# ucus_kayit.net
KiCad netlist of a schematic drawn in Altium Designer
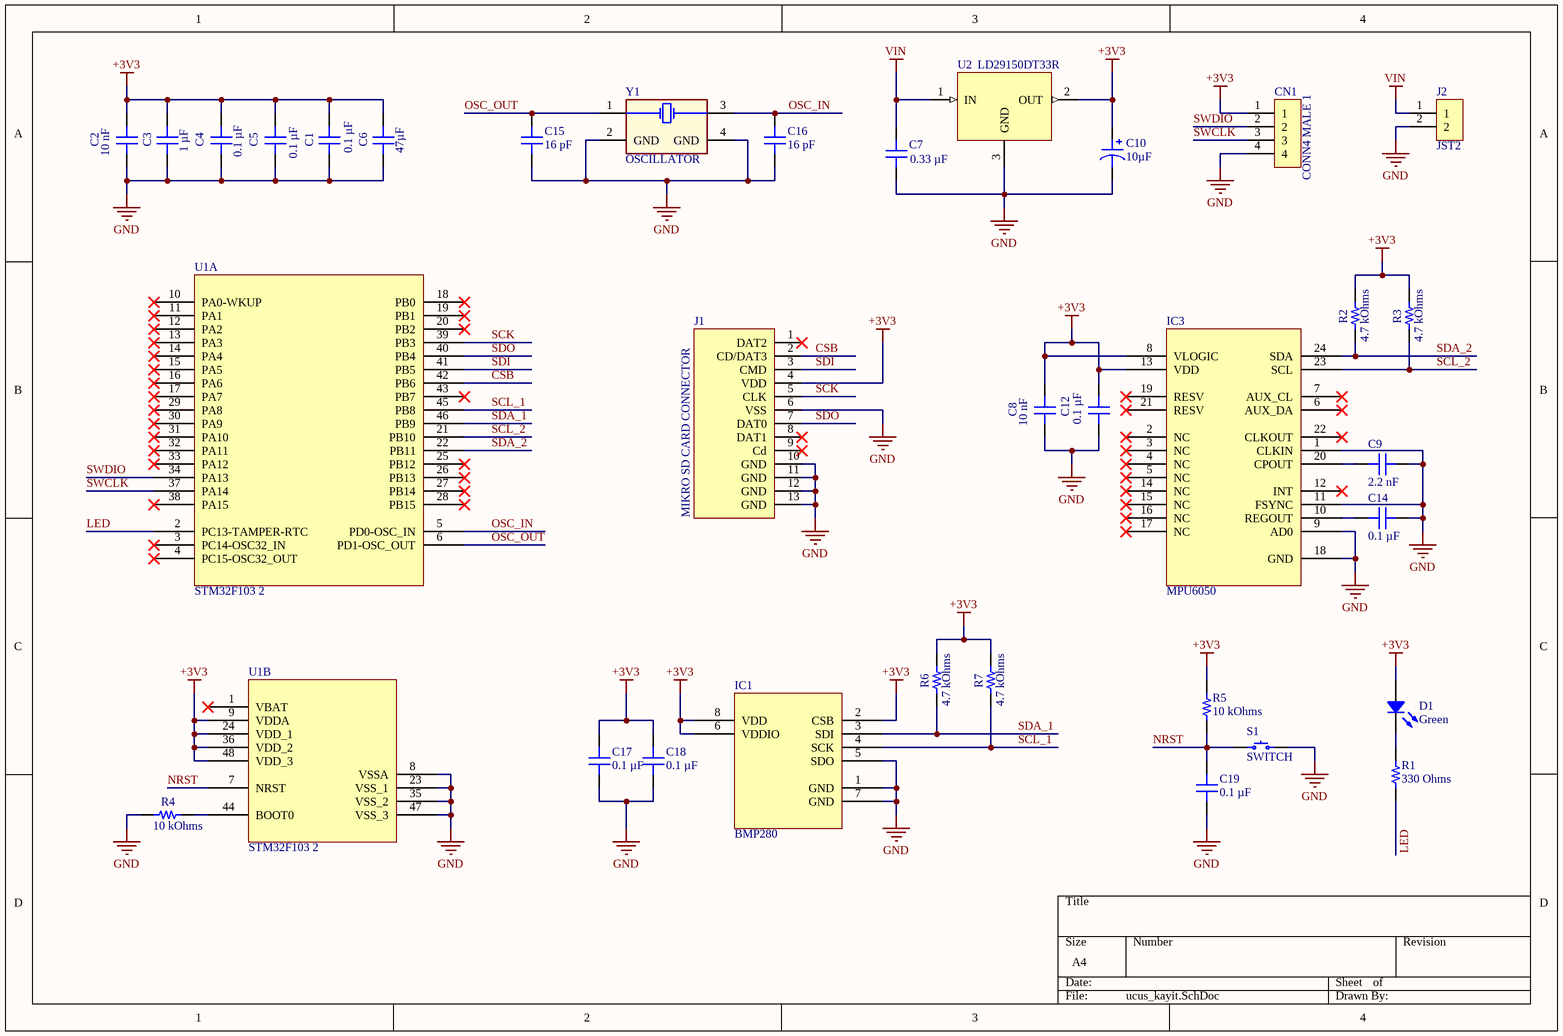
[diagram p0: ucus_kayit.SchDoc]

(export (version "E")
  (design (tool "Eeschema 10.0.6"))
  (components
    (comp (ref "C1")
      (value "0.1 µF")
      (footprint "CAP 1206_3216 - 0.8MM")
      (description "CAP CER 0.1UF 50V X7R 1206")
      (fields
        (field (name "PART NUMBER") "1206B104M500CT")
        (field (name "MANUFACTURER") "Walsin Technology Corporation")
      )
      (libsource (lib "Celestial Altium Library - altium_library") (part "Capacitor"))
    )
    (comp (ref "C2")
      (value "10 nF")
      (footprint "CAP 1206_3216 - 0.8MM")
      (description "CAP CER 1206 10NF 25V C0G 1%")
      (fields (field (name "PART NUMBER") "C1206C103F3GECAUTO") (field (name "MANUFACTURER") "KEMET"))
      (libsource (lib "Celestial Altium Library - altium_library") (part "Capacitor"))
    )
    (comp (ref "C3")
      (value "1 µF")
      (footprint "CAP 1206_3216 - 0.8MM")
      (description "CAP CER 1206 1UF 25V X7R")
      (fields (field (name "PART NUMBER") "C1206X105K3RAC3316") (field (name "MANUFACTURER") "KEMET"))
      (libsource (lib "Celestial Altium Library - altium_library") (part "Capacitor"))
    )
    (comp (ref "C4")
      (value "0.1 µF")
      (footprint "CAP 1206_3216 - 0.8MM")
      (description "CAP CER 0.1UF 50V X7R 1206")
      (fields
        (field (name "PART NUMBER") "1206B104M500CT")
        (field (name "MANUFACTURER") "Walsin Technology Corporation")
      )
      (libsource (lib "Celestial Altium Library - altium_library") (part "Capacitor"))
    )
    (comp (ref "C5")
      (value "0.1 µF")
      (footprint "CAP 1206_3216 - 0.8MM")
      (description "CAP CER 0.1UF 50V X7R 1206")
      (fields
        (field (name "PART NUMBER") "1206B104M500CT")
        (field (name "MANUFACTURER") "Walsin Technology Corporation")
      )
      (libsource (lib "Celestial Altium Library - altium_library") (part "Capacitor"))
    )
    (comp (ref "C6")
      (value "47µF")
      (footprint "CAP 1206_3216 - 1.8MM")
      (description "CAP CER 47UF 6.3V X5R 1206")
      (fields (field (name "PART NUMBER") "12066D476MAT2A") (field (name "MANUFACTURER") "AVX Corporation"))
      (libsource (lib "Celestial Altium Library - altium_library") (part "Capacitor"))
    )
    (comp (ref "C7")
      (value "0.33 µF")
      (footprint "CAP 1206_3216 - 0.8MM")
      (description "CAP CER 0.33UF 25V X7R 1206")
      (fields (field (name "PART NUMBER") "C1206X334K3RAC7800") (field (name "MANUFACTURER") "KEMET"))
      (libsource (lib "Celestial Altium Library - altium_library") (part "Capacitor"))
    )
    (comp (ref "C8")
      (value "10 nF")
      (footprint "CAP 1206_3216 - 0.8MM")
      (description "CAP CER 1206 10NF 25V C0G 1%")
      (fields (field (name "PART NUMBER") "C1206C103F3GECAUTO") (field (name "MANUFACTURER") "KEMET"))
      (libsource (lib "Celestial Altium Library - altium_library") (part "Capacitor"))
    )
    (comp (ref "C9")
      (value "2.2 nF")
      (footprint "CAP 1206_3216 - 0.8MM")
      (description "CAP CER 1206 2.2NF 50V C0G 10%")
      (fields (field (name "PART NUMBER") "C1206C222K5GEC7210") (field (name "MANUFACTURER") "KEMET"))
      (libsource (lib "Celestial Altium Library - altium_library") (part "Capacitor"))
    )
    (comp (ref "C10")
      (value "10µF")
      (footprint "CAP POL 1206_3216")
      (description "CAP TANT 10UF 20% 25V 1206")
      (fields (field (name "PART NUMBER") "F951E106MAAAQ2") (field (name "MANUFACTURER") "AVX Corporation"))
      (libsource (lib "Celestial Altium Library - altium_library") (part "Polarised Capacitor"))
    )
    (comp (ref "C12")
      (value "0.1 µF")
      (footprint "CAP 1206_3216 - 0.8MM")
      (description "CAP CER 0.1UF 50V X7R 1206")
      (fields
        (field (name "PART NUMBER") "1206B104M500CT")
        (field (name "MANUFACTURER") "Walsin Technology Corporation")
      )
      (libsource (lib "Celestial Altium Library - altium_library") (part "Capacitor"))
    )
    (comp (ref "C14")
      (value "0.1 µF")
      (footprint "CAP 1206_3216 - 0.8MM")
      (description "CAP CER 0.1UF 50V X7R 1206")
      (fields
        (field (name "PART NUMBER") "1206B104M500CT")
        (field (name "MANUFACTURER") "Walsin Technology Corporation")
      )
      (libsource (lib "Celestial Altium Library - altium_library") (part "Capacitor"))
    )
    (comp (ref "C15")
      (value "16 pF")
      (footprint "CAP 1206_3216 - 0.8MM")
      (description "CAP CER 16PF 50V NP0 1206")
      (fields (field (name "PART NUMBER") "C1206C160J5GAC7800") (field (name "MANUFACTURER") "KEMET"))
      (libsource (lib "Celestial Altium Library - altium_library") (part "Capacitor"))
    )
    (comp (ref "C16")
      (value "16 pF")
      (footprint "CAP 1206_3216 - 0.8MM")
      (description "CAP CER 16PF 50V NP0 1206")
      (fields (field (name "PART NUMBER") "C1206C160J5GAC7800") (field (name "MANUFACTURER") "KEMET"))
      (libsource (lib "Celestial Altium Library - altium_library") (part "Capacitor"))
    )
    (comp (ref "C17")
      (value "0.1 µF")
      (footprint "CAP 1206_3216 - 0.8MM")
      (description "CAP CER 0.1UF 50V X7R 1206")
      (fields
        (field (name "PART NUMBER") "1206B104M500CT")
        (field (name "MANUFACTURER") "Walsin Technology Corporation")
      )
      (libsource (lib "Celestial Altium Library - altium_library") (part "Capacitor"))
    )
    (comp (ref "C18")
      (value "0.1 µF")
      (footprint "CAP 1206_3216 - 0.8MM")
      (description "CAP CER 0.1UF 50V X7R 1206")
      (fields
        (field (name "PART NUMBER") "1206B104M500CT")
        (field (name "MANUFACTURER") "Walsin Technology Corporation")
      )
      (libsource (lib "Celestial Altium Library - altium_library") (part "Capacitor"))
    )
    (comp (ref "C19")
      (value "0.1 µF")
      (footprint "CAP 1206_3216 - 0.8MM")
      (description "CAP CER 0.1UF 50V X7R 1206")
      (fields
        (field (name "PART NUMBER") "1206B104M500CT")
        (field (name "MANUFACTURER") "Walsin Technology Corporation")
      )
      (libsource (lib "Celestial Altium Library - altium_library") (part "Capacitor"))
    )
    (comp (ref "CN1")
      (value "CONN4 MALE 1")
      (footprint "CONN4 MALE 1")
      (description "4 PIN 2.54MM")
      (libsource (lib "UcusKontrol_Library") (part "CONN4 MALE 1"))
    )
    (comp (ref "D1")
      (value "Green")
      (footprint "LED 0805_2012 GREEN")
      (description "LED GREEN 0805 SMD")
      (fields (field (name "PART NUMBER") "5975316507F") (field (name "MANUFACTURER") "Dialight"))
      (libsource (lib "Celestial Altium Library - altium_library") (part "LED"))
    )
    (comp (ref "IC1") (value "BMP280") (footprint "BMP280") (libsource (lib "ucus_kayit") (part "BMP280")))
    (comp (ref "IC3")
      (value "MPU6050")
      (footprint "QFN")
      (description "IC-6050 SENSOR MOTION QFN24")
      (libsource (lib "UcusKontrol_Library") (part "MPU6050"))
    )
    (comp (ref "J1")
      (value "MIKRO SD CARD CONNECTOR")
      (footprint "MICRO SD CARD CONNECTOR")
      (libsource (lib "UcusKontrol_Library") (part "MIKRO SD CARD CONNECTOR"))
    )
    (comp (ref "J2")
      (value "JST2")
      (footprint "JST2")
      (description "2 PIN 2.54MM")
      (libsource (lib "UcusKontrol_Library") (part "JST2"))
    )
    (comp (ref "R1")
      (value "330 Ohms")
      (footprint "RES 1206_3216")
      (description "RES 330 OHM 5% 1/4W 1206")
      (fields (field (name "PART NUMBER") "RC1206JR-07330RL") (field (name "MANUFACTURER") "Yageo"))
      (libsource (lib "Celestial Altium Library - altium_library") (part "Resistor"))
    )
    (comp (ref "R2")
      (value "4.7 kOhms")
      (footprint "RES 1206_3216")
      (description "RES 4.7K OHM 0.1% 2/5W 1206")
      (fields (field (name "PART NUMBER") "TNPW12064K70BEEA") (field (name "MANUFACTURER") "Vishay Dale"))
      (libsource (lib "Celestial Altium Library - altium_library") (part "Resistor"))
    )
    (comp (ref "R3")
      (value "4.7 kOhms")
      (footprint "RES 1206_3216")
      (description "RES 4.7K OHM 0.1% 2/5W 1206")
      (fields (field (name "PART NUMBER") "TNPW12064K70BEEA") (field (name "MANUFACTURER") "Vishay Dale"))
      (libsource (lib "Celestial Altium Library - altium_library") (part "Resistor"))
    )
    (comp (ref "R4")
      (value "10 kOhms")
      (footprint "RES 1206_3216")
      (description "RES SMD 10K OHM 1% 1/4W 1206")
      (fields (field (name "PART NUMBER") "CRCW120610K0FKTA") (field (name "MANUFACTURER") "Vishay Dale"))
      (libsource (lib "Celestial Altium Library - altium_library") (part "Resistor"))
    )
    (comp (ref "R5")
      (value "10 kOhms")
      (footprint "RES 1206_3216")
      (description "RES SMD 10K OHM 1% 1/4W 1206")
      (fields (field (name "PART NUMBER") "CRCW120610K0FKTA") (field (name "MANUFACTURER") "Vishay Dale"))
      (libsource (lib "Celestial Altium Library - altium_library") (part "Resistor"))
    )
    (comp (ref "R6")
      (value "4.7 kOhms")
      (footprint "RES 1206_3216")
      (description "RES 4.7K OHM 0.1% 2/5W 1206")
      (fields (field (name "PART NUMBER") "TNPW12064K70BEEA") (field (name "MANUFACTURER") "Vishay Dale"))
      (libsource (lib "Celestial Altium Library - altium_library") (part "Resistor"))
    )
    (comp (ref "R7")
      (value "4.7 kOhms")
      (footprint "RES 1206_3216")
      (description "RES 4.7K OHM 0.1% 2/5W 1206")
      (fields (field (name "PART NUMBER") "TNPW12064K70BEEA") (field (name "MANUFACTURER") "Vishay Dale"))
      (libsource (lib "Celestial Altium Library - altium_library") (part "Resistor"))
    )
    (comp (ref "S1")
      (value "SWITCH")
      (footprint "TE FSMSMTR")
      (description "SMD 2 Pin Switch")
      (libsource (lib "ucus_kayit") (part "TACT SWITCH"))
    )
    (comp (ref "U1")
      (value "STM32F103 2")
      (footprint "LQFP48")
      (libsource (lib "UcusKontrol_Library") (part "STM32F103 2"))
    )
    (comp (ref "U2")
      (value "LD29150DT33R")
      (footprint "TO252-3")
      (description "3V3")
      (libsource (lib "ucus_kayit") (part "LD29150DT33R"))
    )
    (comp (ref "Y1")
      (value "OSCILLATOR")
      (footprint "OSCILLATOR")
      (description "8MHZ 12.5pF")
      (libsource (lib "UcusKontrol_Library") (part "OSCILLATOR"))
    )
  )
  (nets
    (net (code "1") (name "+3V3") (class "Default")
      (node (ref "C1") (pin "2") (pinfunction "2_2") (pintype "passive"))
      (node (ref "C10") (pin "1") (pinfunction "1_1") (pintype "passive"))
      (node (ref "C12") (pin "1") (pinfunction "1_1") (pintype "passive"))
      (node (ref "C17") (pin "2") (pinfunction "2_2") (pintype "passive"))
      (node (ref "C18") (pin "2") (pinfunction "2_2") (pintype "passive"))
      (node (ref "C2") (pin "2") (pinfunction "2_2") (pintype "passive"))
      (node (ref "C3") (pin "2") (pinfunction "2_2") (pintype "passive"))
      (node (ref "C4") (pin "2") (pinfunction "2_2") (pintype "passive"))
      (node (ref "C5") (pin "2") (pinfunction "2_2") (pintype "passive"))
      (node (ref "C6") (pin "2") (pinfunction "2_2") (pintype "passive"))
      (node (ref "C8") (pin "2") (pinfunction "2_2") (pintype "passive"))
      (node (ref "CN1") (pin "1") (pinfunction "1_1") (pintype "passive"))
      (node (ref "D1") (pin "1") (pinfunction "1_1") (pintype "passive"))
      (node (ref "IC1") (pin "2") (pinfunction "CSB_2") (pintype "passive"))
      (node (ref "IC1") (pin "6") (pinfunction "VDDIO_6") (pintype "passive"))
      (node (ref "IC1") (pin "8") (pinfunction "VDD_8") (pintype "passive"))
      (node (ref "IC3") (pin "13") (pinfunction "VDD_13") (pintype "passive"))
      (node (ref "IC3") (pin "8") (pinfunction "VLOGIC_8") (pintype "passive"))
      (node (ref "J1") (pin "4") (pinfunction "VDD_4") (pintype "passive"))
      (node (ref "R2") (pin "2") (pinfunction "2_2") (pintype "passive"))
      (node (ref "R3") (pin "2") (pinfunction "2_2") (pintype "passive"))
      (node (ref "R5") (pin "2") (pinfunction "2_2") (pintype "passive"))
      (node (ref "R6") (pin "2") (pinfunction "2_2") (pintype "passive"))
      (node (ref "R7") (pin "2") (pinfunction "2_2") (pintype "passive"))
      (node (ref "U1") (pin "24") (pinfunction "VDD_1_24") (pintype "passive"))
      (node (ref "U1") (pin "36") (pinfunction "VDD_2_36") (pintype "passive"))
      (node (ref "U1") (pin "48") (pinfunction "VDD_3_48") (pintype "passive"))
      (node (ref "U1") (pin "9") (pinfunction "VDDA_9") (pintype "passive"))
      (node (ref "U2") (pin "2") (pinfunction "OUT_2") (pintype "output"))
    )
    (net (code "2") (name "/CSB") (class "Default")
      (node (ref "J1") (pin "2") (pinfunction "CD/DAT3_2") (pintype "passive"))
      (node (ref "U1") (pin "42") (pinfunction "PB6_42") (pintype "passive"))
    )
    (net (code "3") (name "/LED") (class "Default")
      (node (ref "R1") (pin "2") (pinfunction "2_2") (pintype "passive"))
      (node (ref "U1") (pin "2") (pinfunction "PC13-TAMPER-RTC_2") (pintype "passive"))
    )
    (net (code "4") (name "/NRST") (class "Default")
      (node (ref "C19") (pin "2") (pinfunction "2_2") (pintype "passive"))
      (node (ref "R5") (pin "1") (pinfunction "1_1") (pintype "passive"))
      (node (ref "S1") (pin "1") (pinfunction "1_1") (pintype "passive"))
      (node (ref "U1") (pin "7") (pinfunction "NRST_7") (pintype "passive"))
    )
    (net (code "5") (name "/OSC_IN") (class "Default")
      (node (ref "C16") (pin "1") (pinfunction "1_1") (pintype "passive"))
      (node (ref "U1") (pin "5") (pinfunction "PD0-OSC_IN_5") (pintype "passive"))
      (node (ref "Y1") (pin "3") (pintype "passive"))
    )
    (net (code "6") (name "/OSC_OUT") (class "Default")
      (node (ref "C15") (pin "1") (pinfunction "1_1") (pintype "passive"))
      (node (ref "U1") (pin "6") (pinfunction "PD1-OSC_OUT_6") (pintype "passive"))
      (node (ref "Y1") (pin "1") (pintype "power_in"))
    )
    (net (code "7") (name "/SCK") (class "Default")
      (node (ref "J1") (pin "5") (pinfunction "CLK_5") (pintype "passive"))
      (node (ref "U1") (pin "39") (pinfunction "PB3_39") (pintype "passive"))
    )
    (net (code "8") (name "/SCL_1") (class "Default")
      (node (ref "IC1") (pin "4") (pinfunction "SCK_4") (pintype "passive"))
      (node (ref "R7") (pin "1") (pinfunction "1_1") (pintype "passive"))
      (node (ref "U1") (pin "45") (pinfunction "PB8_45") (pintype "passive"))
    )
    (net (code "9") (name "/SCL_2") (class "Default")
      (node (ref "IC3") (pin "23") (pinfunction "SCL_23") (pintype "passive"))
      (node (ref "R3") (pin "1") (pinfunction "1_1") (pintype "passive"))
      (node (ref "U1") (pin "21") (pinfunction "PB10_21") (pintype "passive"))
    )
    (net (code "10") (name "/SDA_1") (class "Default")
      (node (ref "IC1") (pin "3") (pinfunction "SDI_3") (pintype "passive"))
      (node (ref "R6") (pin "1") (pinfunction "1_1") (pintype "passive"))
      (node (ref "U1") (pin "46") (pinfunction "PB9_46") (pintype "passive"))
    )
    (net (code "11") (name "/SDA_2") (class "Default")
      (node (ref "IC3") (pin "24") (pinfunction "SDA_24") (pintype "passive"))
      (node (ref "R2") (pin "1") (pinfunction "1_1") (pintype "passive"))
      (node (ref "U1") (pin "22") (pinfunction "PB11_22") (pintype "passive"))
    )
    (net (code "12") (name "/SDI") (class "Default")
      (node (ref "J1") (pin "3") (pinfunction "CMD_3") (pintype "passive"))
      (node (ref "U1") (pin "41") (pinfunction "PB5_41") (pintype "passive"))
    )
    (net (code "13") (name "/SDO") (class "Default")
      (node (ref "J1") (pin "7") (pinfunction "DAT0_7") (pintype "passive"))
      (node (ref "U1") (pin "40") (pinfunction "PB4_40") (pintype "passive"))
    )
    (net (code "14") (name "/SWCLK") (class "Default")
      (node (ref "CN1") (pin "3") (pinfunction "3_3") (pintype "passive"))
      (node (ref "U1") (pin "37") (pinfunction "PA14_37") (pintype "passive"))
    )
    (net (code "15") (name "/SWDIO") (class "Default")
      (node (ref "CN1") (pin "2") (pinfunction "2_2") (pintype "passive"))
      (node (ref "U1") (pin "34") (pinfunction "PA13_34") (pintype "passive"))
    )
    (net (code "16") (name "GND") (class "Default")
      (node (ref "C1") (pin "1") (pinfunction "1_1") (pintype "passive"))
      (node (ref "C10") (pin "2") (pinfunction "2_2") (pintype "passive"))
      (node (ref "C12") (pin "2") (pinfunction "2_2") (pintype "passive"))
      (node (ref "C14") (pin "2") (pinfunction "2_2") (pintype "passive"))
      (node (ref "C15") (pin "2") (pinfunction "2_2") (pintype "passive"))
      (node (ref "C16") (pin "2") (pinfunction "2_2") (pintype "passive"))
      (node (ref "C17") (pin "1") (pinfunction "1_1") (pintype "passive"))
      (node (ref "C18") (pin "1") (pinfunction "1_1") (pintype "passive"))
      (node (ref "C19") (pin "1") (pinfunction "1_1") (pintype "passive"))
      (node (ref "C2") (pin "1") (pinfunction "1_1") (pintype "passive"))
      (node (ref "C3") (pin "1") (pinfunction "1_1") (pintype "passive"))
      (node (ref "C4") (pin "1") (pinfunction "1_1") (pintype "passive"))
      (node (ref "C5") (pin "1") (pinfunction "1_1") (pintype "passive"))
      (node (ref "C6") (pin "1") (pinfunction "1_1") (pintype "passive"))
      (node (ref "C7") (pin "1") (pinfunction "1_1") (pintype "passive"))
      (node (ref "C8") (pin "1") (pinfunction "1_1") (pintype "passive"))
      (node (ref "C9") (pin "2") (pinfunction "2_2") (pintype "passive"))
      (node (ref "CN1") (pin "4") (pinfunction "4_4") (pintype "passive"))
      (node (ref "IC1") (pin "1") (pinfunction "GND_1") (pintype "passive"))
      (node (ref "IC1") (pin "5") (pinfunction "SDO_5") (pintype "passive"))
      (node (ref "IC1") (pin "7") (pinfunction "GND_7") (pintype "passive"))
      (node (ref "IC3") (pin "1") (pinfunction "CLKIN_1") (pintype "passive"))
      (node (ref "IC3") (pin "11") (pinfunction "FSYNC_11") (pintype "passive"))
      (node (ref "IC3") (pin "18") (pinfunction "GND_18") (pintype "passive"))
      (node (ref "IC3") (pin "9") (pinfunction "AD0_9") (pintype "passive"))
      (node (ref "J1") (pin "10") (pinfunction "GND_10") (pintype "passive"))
      (node (ref "J1") (pin "11") (pinfunction "GND_11") (pintype "passive"))
      (node (ref "J1") (pin "12") (pinfunction "GND_12") (pintype "passive"))
      (node (ref "J1") (pin "13") (pinfunction "GND_13") (pintype "passive"))
      (node (ref "J1") (pin "6") (pinfunction "VSS_6") (pintype "passive"))
      (node (ref "J2") (pin "2") (pinfunction "2_2") (pintype "passive"))
      (node (ref "R4") (pin "1") (pinfunction "1_1") (pintype "passive"))
      (node (ref "S1") (pin "2") (pinfunction "2_2") (pintype "passive"))
      (node (ref "U1") (pin "23") (pinfunction "VSS_1_23") (pintype "passive"))
      (node (ref "U1") (pin "35") (pinfunction "VSS_2_35") (pintype "passive"))
      (node (ref "U1") (pin "47") (pinfunction "VSS_3_47") (pintype "passive"))
      (node (ref "U1") (pin "8") (pinfunction "VSSA_8") (pintype "passive"))
      (node (ref "U2") (pin "3") (pinfunction "GND_3") (pintype "passive"))
      (node (ref "Y1") (pin "2") (pinfunction "GND_2") (pintype "power_in"))
      (node (ref "Y1") (pin "4") (pinfunction "GND_4") (pintype "passive"))
    )
    (net (code "17") (name "Net-(D1-Pad2)") (class "Default")
      (node (ref "D1") (pin "2") (pinfunction "2_2") (pintype "passive"))
      (node (ref "R1") (pin "1") (pinfunction "1_1") (pintype "passive"))
    )
    (net (code "18") (name "Net-(IC3-CPOUT)") (class "Default")
      (node (ref "C9") (pin "1") (pinfunction "1_1") (pintype "passive"))
      (node (ref "IC3") (pin "20") (pinfunction "CPOUT_20") (pintype "passive"))
    )
    (net (code "19") (name "Net-(IC3-REGOUT)") (class "Default")
      (node (ref "C14") (pin "1") (pinfunction "1_1") (pintype "passive"))
      (node (ref "IC3") (pin "10") (pinfunction "REGOUT_10") (pintype "passive"))
    )
    (net (code "20") (name "Net-(U1B-BOOT0)") (class "Default")
      (node (ref "R4") (pin "2") (pinfunction "2_2") (pintype "passive"))
      (node (ref "U1") (pin "44") (pinfunction "BOOT0_44") (pintype "passive"))
    )
    (net (code "21") (name "VIN") (class "Default")
      (node (ref "C7") (pin "2") (pinfunction "2_2") (pintype "passive"))
      (node (ref "J2") (pin "1") (pinfunction "1_1") (pintype "passive"))
      (node (ref "U2") (pin "1") (pinfunction "IN_1") (pintype "input"))
    )
    (net (code "22") (name "unconnected-(IC3-AUX_CL-Pad7)") (class "Default")
      (node (ref "IC3") (pin "7") (pinfunction "AUX_CL_7") (pintype "passive+no_connect"))
    )
    (net (code "23") (name "unconnected-(IC3-AUX_DA-Pad6)") (class "Default")
      (node (ref "IC3") (pin "6") (pinfunction "AUX_DA_6") (pintype "passive+no_connect"))
    )
    (net (code "24") (name "unconnected-(IC3-CLKOUT-Pad22)") (class "Default")
      (node (ref "IC3") (pin "22") (pinfunction "CLKOUT_22") (pintype "passive+no_connect"))
    )
    (net (code "25") (name "unconnected-(IC3-INT-Pad12)") (class "Default")
      (node (ref "IC3") (pin "12") (pinfunction "INT_12") (pintype "passive+no_connect"))
    )
    (net (code "26") (name "unconnected-(IC3-NC-Pad2)") (class "Default")
      (node (ref "IC3") (pin "2") (pinfunction "NC_2") (pintype "passive+no_connect"))
    )
    (net (code "27") (name "unconnected-(IC3-NC-Pad3)") (class "Default")
      (node (ref "IC3") (pin "3") (pinfunction "NC_3") (pintype "passive+no_connect"))
    )
    (net (code "28") (name "unconnected-(IC3-NC-Pad4)") (class "Default")
      (node (ref "IC3") (pin "4") (pinfunction "NC_4") (pintype "passive+no_connect"))
    )
    (net (code "29") (name "unconnected-(IC3-NC-Pad5)") (class "Default")
      (node (ref "IC3") (pin "5") (pinfunction "NC_5") (pintype "passive+no_connect"))
    )
    (net (code "30") (name "unconnected-(IC3-NC-Pad14)") (class "Default")
      (node (ref "IC3") (pin "14") (pinfunction "NC_14") (pintype "passive+no_connect"))
    )
    (net (code "31") (name "unconnected-(IC3-NC-Pad15)") (class "Default")
      (node (ref "IC3") (pin "15") (pinfunction "NC_15") (pintype "passive+no_connect"))
    )
    (net (code "32") (name "unconnected-(IC3-NC-Pad16)") (class "Default")
      (node (ref "IC3") (pin "16") (pinfunction "NC_16") (pintype "passive+no_connect"))
    )
    (net (code "33") (name "unconnected-(IC3-NC-Pad17)") (class "Default")
      (node (ref "IC3") (pin "17") (pinfunction "NC_17") (pintype "passive+no_connect"))
    )
    (net (code "34") (name "unconnected-(IC3-RESV-Pad19)") (class "Default")
      (node (ref "IC3") (pin "19") (pinfunction "RESV_19") (pintype "passive+no_connect"))
    )
    (net (code "35") (name "unconnected-(IC3-RESV-Pad21)") (class "Default")
      (node (ref "IC3") (pin "21") (pinfunction "RESV_21") (pintype "passive+no_connect"))
    )
    (net (code "36") (name "unconnected-(J1-Cd-Pad9)") (class "Default")
      (node (ref "J1") (pin "9") (pinfunction "Cd_9") (pintype "passive+no_connect"))
    )
    (net (code "37") (name "unconnected-(J1-DAT1-Pad8)") (class "Default")
      (node (ref "J1") (pin "8") (pinfunction "DAT1_8") (pintype "passive+no_connect"))
    )
    (net (code "38") (name "unconnected-(J1-DAT2-Pad1)") (class "Default")
      (node (ref "J1") (pin "1") (pinfunction "DAT2_1") (pintype "passive+no_connect"))
    )
    (net (code "39") (name "unconnected-(U1A-PA0-WKUP-Pad10)") (class "Default")
      (node (ref "U1") (pin "10") (pinfunction "PA0-WKUP_10") (pintype "passive+no_connect"))
    )
    (net (code "40") (name "unconnected-(U1A-PA1-Pad11)") (class "Default")
      (node (ref "U1") (pin "11") (pinfunction "PA1_11") (pintype "passive+no_connect"))
    )
    (net (code "41") (name "unconnected-(U1A-PA2-Pad12)") (class "Default")
      (node (ref "U1") (pin "12") (pinfunction "PA2_12") (pintype "passive+no_connect"))
    )
    (net (code "42") (name "unconnected-(U1A-PA3-Pad13)") (class "Default")
      (node (ref "U1") (pin "13") (pinfunction "PA3_13") (pintype "passive+no_connect"))
    )
    (net (code "43") (name "unconnected-(U1A-PA4-Pad14)") (class "Default")
      (node (ref "U1") (pin "14") (pinfunction "PA4_14") (pintype "passive+no_connect"))
    )
    (net (code "44") (name "unconnected-(U1A-PA5-Pad15)") (class "Default")
      (node (ref "U1") (pin "15") (pinfunction "PA5_15") (pintype "passive+no_connect"))
    )
    (net (code "45") (name "unconnected-(U1A-PA6-Pad16)") (class "Default")
      (node (ref "U1") (pin "16") (pinfunction "PA6_16") (pintype "passive+no_connect"))
    )
    (net (code "46") (name "unconnected-(U1A-PA7-Pad17)") (class "Default")
      (node (ref "U1") (pin "17") (pinfunction "PA7_17") (pintype "passive+no_connect"))
    )
    (net (code "47") (name "unconnected-(U1A-PA8-Pad29)") (class "Default")
      (node (ref "U1") (pin "29") (pinfunction "PA8_29") (pintype "passive+no_connect"))
    )
    (net (code "48") (name "unconnected-(U1A-PA9-Pad30)") (class "Default")
      (node (ref "U1") (pin "30") (pinfunction "PA9_30") (pintype "passive+no_connect"))
    )
    (net (code "49") (name "unconnected-(U1A-PA10-Pad31)") (class "Default")
      (node (ref "U1") (pin "31") (pinfunction "PA10_31") (pintype "passive+no_connect"))
    )
    (net (code "50") (name "unconnected-(U1A-PA11-Pad32)") (class "Default")
      (node (ref "U1") (pin "32") (pinfunction "PA11_32") (pintype "passive+no_connect"))
    )
    (net (code "51") (name "unconnected-(U1A-PA12-Pad33)") (class "Default")
      (node (ref "U1") (pin "33") (pinfunction "PA12_33") (pintype "passive+no_connect"))
    )
    (net (code "52") (name "unconnected-(U1A-PA15-Pad38)") (class "Default")
      (node (ref "U1") (pin "38") (pinfunction "PA15_38") (pintype "passive+no_connect"))
    )
    (net (code "53") (name "unconnected-(U1A-PB0-Pad18)") (class "Default")
      (node (ref "U1") (pin "18") (pinfunction "PB0_18") (pintype "passive+no_connect"))
    )
    (net (code "54") (name "unconnected-(U1A-PB1-Pad19)") (class "Default")
      (node (ref "U1") (pin "19") (pinfunction "PB1_19") (pintype "passive+no_connect"))
    )
    (net (code "55") (name "unconnected-(U1A-PB2-Pad20)") (class "Default")
      (node (ref "U1") (pin "20") (pinfunction "PB2_20") (pintype "passive+no_connect"))
    )
    (net (code "56") (name "unconnected-(U1A-PB7-Pad43)") (class "Default")
      (node (ref "U1") (pin "43") (pinfunction "PB7_43") (pintype "passive+no_connect"))
    )
    (net (code "57") (name "unconnected-(U1A-PB12-Pad25)") (class "Default")
      (node (ref "U1") (pin "25") (pinfunction "PB12_25") (pintype "passive+no_connect"))
    )
    (net (code "58") (name "unconnected-(U1A-PB13-Pad26)") (class "Default")
      (node (ref "U1") (pin "26") (pinfunction "PB13_26") (pintype "passive+no_connect"))
    )
    (net (code "59") (name "unconnected-(U1A-PB14-Pad27)") (class "Default")
      (node (ref "U1") (pin "27") (pinfunction "PB14_27") (pintype "passive+no_connect"))
    )
    (net (code "60") (name "unconnected-(U1A-PB15-Pad28)") (class "Default")
      (node (ref "U1") (pin "28") (pinfunction "PB15_28") (pintype "passive+no_connect"))
    )
    (net (code "61") (name "unconnected-(U1A-PC14-OSC32_IN-Pad3)") (class "Default")
      (node (ref "U1") (pin "3") (pinfunction "PC14-OSC32_IN_3") (pintype "passive+no_connect"))
    )
    (net (code "62") (name "unconnected-(U1A-PC15-OSC32_OUT-Pad4)") (class "Default")
      (node (ref "U1") (pin "4") (pinfunction "PC15-OSC32_OUT_4") (pintype "passive+no_connect"))
    )
    (net (code "63") (name "unconnected-(U1B-VBAT-Pad1)") (class "Default")
      (node (ref "U1") (pin "1") (pinfunction "VBAT_1") (pintype "passive+no_connect"))
    )
  )
)
